# OPA4377.net
KiCad netlist of a schematic drawn in Altium Designer
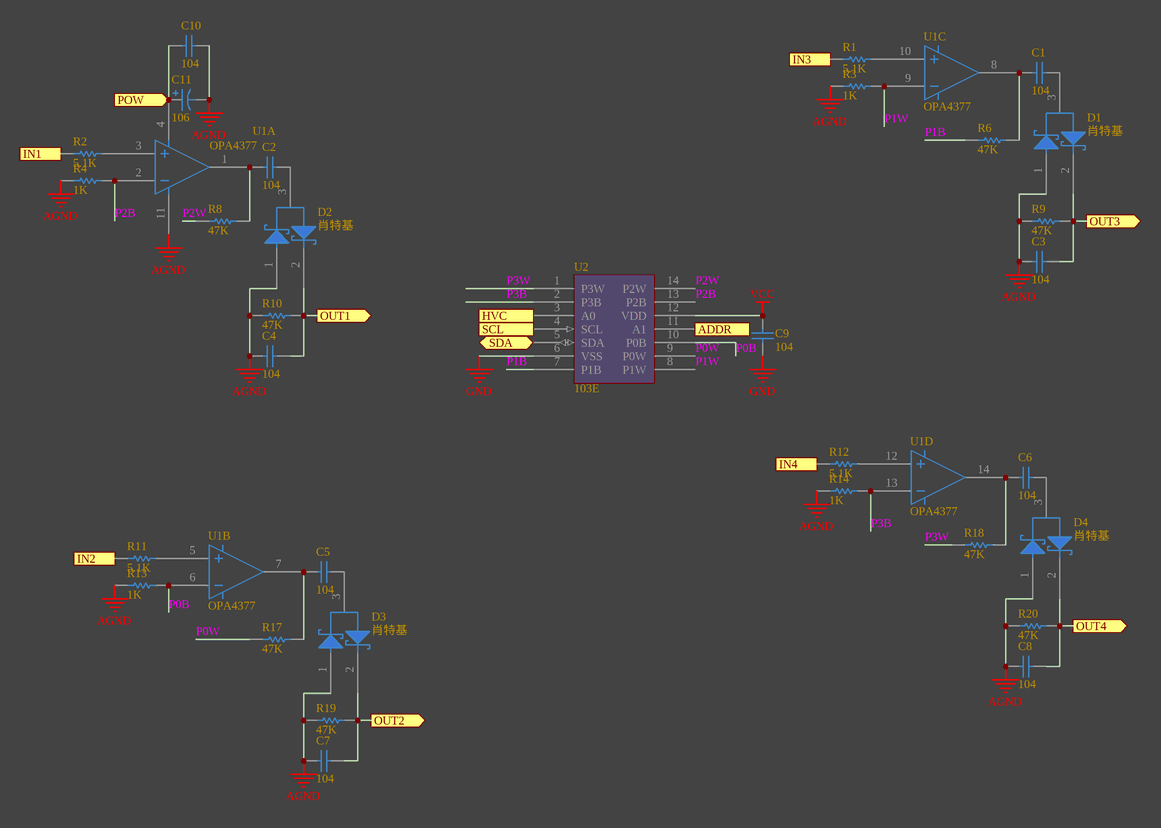
[diagram p0: OPA4377.SchDoc]

(export (version "E")
  (design (tool "Eeschema 10.0.6"))
  (components
    (comp (ref "C1")
      (value "104")
      (footprint "C0402")
      (description "Capacitor")
      (fields (field (name "PUBLISHER") "Altium Limited"))
      (libsource (lib "iMag") (part "电容"))
    )
    (comp (ref "C2")
      (value "104")
      (footprint "C0402")
      (description "Capacitor")
      (fields (field (name "PUBLISHER") "Altium Limited"))
      (libsource (lib "iMag") (part "电容"))
    )
    (comp (ref "C3")
      (value "104")
      (footprint "C0402")
      (description "Capacitor")
      (fields (field (name "PUBLISHER") "Altium Limited"))
      (libsource (lib "iMag") (part "电容"))
    )
    (comp (ref "C4")
      (value "104")
      (footprint "C0402")
      (description "Capacitor")
      (fields (field (name "PUBLISHER") "Altium Limited"))
      (libsource (lib "iMag") (part "电容"))
    )
    (comp (ref "C5")
      (value "104")
      (footprint "C0402")
      (description "Capacitor")
      (fields (field (name "PUBLISHER") "Altium Limited"))
      (libsource (lib "iMag") (part "电容"))
    )
    (comp (ref "C6")
      (value "104")
      (footprint "C0402")
      (description "Capacitor")
      (fields (field (name "PUBLISHER") "Altium Limited"))
      (libsource (lib "iMag") (part "电容"))
    )
    (comp (ref "C7")
      (value "104")
      (footprint "C0402")
      (description "Capacitor")
      (fields (field (name "PUBLISHER") "Altium Limited"))
      (libsource (lib "iMag") (part "电容"))
    )
    (comp (ref "C8")
      (value "104")
      (footprint "C0402")
      (description "Capacitor")
      (fields (field (name "PUBLISHER") "Altium Limited"))
      (libsource (lib "iMag") (part "电容"))
    )
    (comp (ref "C9")
      (value "104")
      (footprint "C0402")
      (description "Capacitor")
      (fields (field (name "PUBLISHER") "Altium Limited"))
      (libsource (lib "iMag") (part "电容"))
    )
    (comp (ref "C10")
      (value "104")
      (footprint "C0402")
      (description "Capacitor")
      (fields (field (name "PUBLISHER") "Altium Limited"))
      (libsource (lib "iMag") (part "电容"))
    )
    (comp (ref "C11")
      (value "106")
      (footprint "3216-ce")
      (description "Polarized Capacitor (Axial)")
      (fields (field (name "PUBLISHER") "Altium Limited"))
      (libsource (lib "iMag") (part "电解电容"))
    )
    (comp (ref "D1") (value "肖特基") (footprint "SOT-23") (libsource (lib "iMag") (part "BAT54S")))
    (comp (ref "D2") (value "肖特基") (footprint "SOT-23") (libsource (lib "iMag") (part "BAT54S")))
    (comp (ref "D3") (value "肖特基") (footprint "SOT-23") (libsource (lib "iMag") (part "BAT54S")))
    (comp (ref "D4") (value "肖特基") (footprint "SOT-23") (libsource (lib "iMag") (part "BAT54S")))
    (comp (ref "R1")
      (value "5.1K")
      (footprint "R0402")
      (description "Resistor")
      (fields (field (name "PUBLISHER") "Altium Limited"))
      (libsource (lib "iMag") (part "电阻"))
    )
    (comp (ref "R2")
      (value "5.1K")
      (footprint "R0402")
      (description "Resistor")
      (fields (field (name "PUBLISHER") "Altium Limited"))
      (libsource (lib "iMag") (part "电阻"))
    )
    (comp (ref "R3")
      (value "1K")
      (footprint "R0402")
      (description "Resistor")
      (fields (field (name "PUBLISHER") "Altium Limited"))
      (libsource (lib "iMag") (part "电阻"))
    )
    (comp (ref "R4")
      (value "1K")
      (footprint "R0402")
      (description "Resistor")
      (fields (field (name "PUBLISHER") "Altium Limited"))
      (libsource (lib "iMag") (part "电阻"))
    )
    (comp (ref "R6")
      (value "47K")
      (footprint "R0402")
      (description "Resistor")
      (fields (field (name "PUBLISHER") "Altium Limited"))
      (libsource (lib "iMag") (part "电阻"))
    )
    (comp (ref "R8")
      (value "47K")
      (footprint "R0402")
      (description "Resistor")
      (fields (field (name "PUBLISHER") "Altium Limited"))
      (libsource (lib "iMag") (part "电阻"))
    )
    (comp (ref "R9")
      (value "47K")
      (footprint "R0402")
      (description "Resistor")
      (fields (field (name "PUBLISHER") "Altium Limited"))
      (libsource (lib "iMag") (part "电阻"))
    )
    (comp (ref "R10")
      (value "47K")
      (footprint "R0402")
      (description "Resistor")
      (fields (field (name "PUBLISHER") "Altium Limited"))
      (libsource (lib "iMag") (part "电阻"))
    )
    (comp (ref "R11")
      (value "5.1K")
      (footprint "R0402")
      (description "Resistor")
      (fields (field (name "PUBLISHER") "Altium Limited"))
      (libsource (lib "iMag") (part "电阻"))
    )
    (comp (ref "R12")
      (value "5.1K")
      (footprint "R0402")
      (description "Resistor")
      (fields (field (name "PUBLISHER") "Altium Limited"))
      (libsource (lib "iMag") (part "电阻"))
    )
    (comp (ref "R13")
      (value "1K")
      (footprint "R0402")
      (description "Resistor")
      (fields (field (name "PUBLISHER") "Altium Limited"))
      (libsource (lib "iMag") (part "电阻"))
    )
    (comp (ref "R14")
      (value "1K")
      (footprint "R0402")
      (description "Resistor")
      (fields (field (name "PUBLISHER") "Altium Limited"))
      (libsource (lib "iMag") (part "电阻"))
    )
    (comp (ref "R17")
      (value "47K")
      (footprint "R0402")
      (description "Resistor")
      (fields (field (name "PUBLISHER") "Altium Limited"))
      (libsource (lib "iMag") (part "电阻"))
    )
    (comp (ref "R18")
      (value "47K")
      (footprint "R0402")
      (description "Resistor")
      (fields (field (name "PUBLISHER") "Altium Limited"))
      (libsource (lib "iMag") (part "电阻"))
    )
    (comp (ref "R19")
      (value "47K")
      (footprint "R0402")
      (description "Resistor")
      (fields (field (name "PUBLISHER") "Altium Limited"))
      (libsource (lib "iMag") (part "电阻"))
    )
    (comp (ref "R20")
      (value "47K")
      (footprint "R0402")
      (description "Resistor")
      (fields (field (name "PUBLISHER") "Altium Limited"))
      (libsource (lib "iMag") (part "电阻"))
    )
    (comp (ref "U1") (value "OPA4377") (footprint "TSSOP-14") (libsource (lib "iMag") (part "4运放")))
    (comp (ref "U2") (value "103E") (footprint "TSSOP-14") (libsource (lib "iMag") (part "MCP4452")))
  )
  (nets
    (net (code "1") (name "/ADDR") (class "Default")
      (node (ref "U2") (pin "11") (pinfunction "A1_11") (pintype "passive"))
    )
    (net (code "2") (name "/HVC") (class "Default")
      (node (ref "U2") (pin "3") (pinfunction "A0_3") (pintype "passive"))
    )
    (net (code "3") (name "/IN1") (class "Default")
      (node (ref "R2") (pin "2") (pinfunction "2_2") (pintype "passive"))
    )
    (net (code "4") (name "/IN2") (class "Default")
      (node (ref "R11") (pin "2") (pinfunction "2_2") (pintype "passive"))
    )
    (net (code "5") (name "/IN3") (class "Default")
      (node (ref "R1") (pin "2") (pinfunction "2_2") (pintype "passive"))
    )
    (net (code "6") (name "/IN4") (class "Default")
      (node (ref "R12") (pin "2") (pinfunction "2_2") (pintype "passive"))
    )
    (net (code "7") (name "/OUT1") (class "Default")
      (node (ref "C4") (pin "2") (pinfunction "2_2") (pintype "passive"))
      (node (ref "D2") (pin "2") (pinfunction "2_2") (pintype "passive"))
      (node (ref "R10") (pin "1") (pinfunction "1_1") (pintype "passive"))
    )
    (net (code "8") (name "/OUT2") (class "Default")
      (node (ref "C7") (pin "2") (pinfunction "2_2") (pintype "passive"))
      (node (ref "D3") (pin "2") (pinfunction "2_2") (pintype "passive"))
      (node (ref "R19") (pin "1") (pinfunction "1_1") (pintype "passive"))
    )
    (net (code "9") (name "/OUT3") (class "Default")
      (node (ref "C3") (pin "2") (pinfunction "2_2") (pintype "passive"))
      (node (ref "D1") (pin "2") (pinfunction "2_2") (pintype "passive"))
      (node (ref "R9") (pin "1") (pinfunction "1_1") (pintype "passive"))
    )
    (net (code "10") (name "/OUT4") (class "Default")
      (node (ref "C8") (pin "2") (pinfunction "2_2") (pintype "passive"))
      (node (ref "D4") (pin "2") (pinfunction "2_2") (pintype "passive"))
      (node (ref "R20") (pin "1") (pinfunction "1_1") (pintype "passive"))
    )
    (net (code "11") (name "/P0B") (class "Default")
      (node (ref "R13") (pin "1") (pinfunction "1_1") (pintype "passive"))
      (node (ref "U1") (pin "6") (pintype "passive"))
      (node (ref "U2") (pin "10") (pinfunction "P0B_10") (pintype "passive"))
    )
    (net (code "12") (name "/P0W") (class "Default")
      (node (ref "R17") (pin "2") (pinfunction "2_2") (pintype "passive"))
      (node (ref "U2") (pin "9") (pinfunction "P0W_9") (pintype "passive"))
    )
    (net (code "13") (name "/P1B") (class "Default")
      (node (ref "R6") (pin "2") (pinfunction "2_2") (pintype "passive"))
      (node (ref "U2") (pin "7") (pinfunction "P1B_7") (pintype "passive"))
    )
    (net (code "14") (name "/P1W") (class "Default")
      (node (ref "R3") (pin "1") (pinfunction "1_1") (pintype "passive"))
      (node (ref "U1") (pin "9") (pintype "passive"))
      (node (ref "U2") (pin "8") (pinfunction "P1W_8") (pintype "passive"))
    )
    (net (code "15") (name "/P2B") (class "Default")
      (node (ref "R4") (pin "1") (pinfunction "1_1") (pintype "passive"))
      (node (ref "U1") (pin "2") (pintype "passive"))
      (node (ref "U2") (pin "13") (pinfunction "P2B_13") (pintype "passive"))
    )
    (net (code "16") (name "/P2W") (class "Default")
      (node (ref "R8") (pin "2") (pinfunction "2_2") (pintype "passive"))
      (node (ref "U2") (pin "14") (pinfunction "P2W_14") (pintype "passive"))
    )
    (net (code "17") (name "/P3B") (class "Default")
      (node (ref "R14") (pin "1") (pinfunction "1_1") (pintype "passive"))
      (node (ref "U1") (pin "13") (pintype "passive"))
      (node (ref "U2") (pin "2") (pinfunction "P3B_2") (pintype "passive"))
    )
    (net (code "18") (name "/P3W") (class "Default")
      (node (ref "R18") (pin "2") (pinfunction "2_2") (pintype "passive"))
      (node (ref "U2") (pin "1") (pinfunction "P3W_1") (pintype "passive"))
    )
    (net (code "19") (name "/POW") (class "Default")
      (node (ref "C10") (pin "1") (pinfunction "1_1") (pintype "passive"))
      (node (ref "C11") (pin "1") (pinfunction "1_1") (pintype "passive"))
      (node (ref "U1") (pin "4") (pintype "passive"))
    )
    (net (code "20") (name "/SCL") (class "Default")
      (node (ref "U2") (pin "4") (pinfunction "SCL_4") (pintype "input"))
    )
    (net (code "21") (name "/SDA") (class "Default")
      (node (ref "U2") (pin "5") (pinfunction "SDA_5") (pintype "bidirectional"))
    )
    (net (code "22") (name "AGND") (class "Default")
      (node (ref "C10") (pin "2") (pinfunction "2_2") (pintype "passive"))
      (node (ref "C11") (pin "2") (pinfunction "2_2") (pintype "passive"))
      (node (ref "C3") (pin "1") (pinfunction "1_1") (pintype "passive"))
      (node (ref "C4") (pin "1") (pinfunction "1_1") (pintype "passive"))
      (node (ref "C7") (pin "1") (pinfunction "1_1") (pintype "passive"))
      (node (ref "C8") (pin "1") (pinfunction "1_1") (pintype "passive"))
      (node (ref "D1") (pin "1") (pinfunction "1_1") (pintype "passive"))
      (node (ref "D2") (pin "1") (pinfunction "1_1") (pintype "passive"))
      (node (ref "D3") (pin "1") (pinfunction "1_1") (pintype "passive"))
      (node (ref "D4") (pin "1") (pinfunction "1_1") (pintype "passive"))
      (node (ref "R10") (pin "2") (pinfunction "2_2") (pintype "passive"))
      (node (ref "R13") (pin "2") (pinfunction "2_2") (pintype "passive"))
      (node (ref "R14") (pin "2") (pinfunction "2_2") (pintype "passive"))
      (node (ref "R19") (pin "2") (pinfunction "2_2") (pintype "passive"))
      (node (ref "R20") (pin "2") (pinfunction "2_2") (pintype "passive"))
      (node (ref "R3") (pin "2") (pinfunction "2_2") (pintype "passive"))
      (node (ref "R4") (pin "2") (pinfunction "2_2") (pintype "passive"))
      (node (ref "R9") (pin "2") (pinfunction "2_2") (pintype "passive"))
      (node (ref "U1") (pin "11") (pintype "passive"))
    )
    (net (code "23") (name "GND") (class "Default")
      (node (ref "C9") (pin "1") (pinfunction "1_1") (pintype "passive"))
      (node (ref "U2") (pin "6") (pinfunction "VSS_6") (pintype "passive"))
    )
    (net (code "24") (name "Net-(C1-Pad1)") (class "Default")
      (node (ref "C1") (pin "1") (pinfunction "1_1") (pintype "passive"))
      (node (ref "R6") (pin "1") (pinfunction "1_1") (pintype "passive"))
      (node (ref "U1") (pin "8") (pintype "passive"))
    )
    (net (code "25") (name "Net-(C1-Pad2)") (class "Default")
      (node (ref "C1") (pin "2") (pinfunction "2_2") (pintype "passive"))
      (node (ref "D1") (pin "3") (pinfunction "3_3") (pintype "passive"))
    )
    (net (code "26") (name "Net-(C2-Pad1)") (class "Default")
      (node (ref "C2") (pin "1") (pinfunction "1_1") (pintype "passive"))
      (node (ref "R8") (pin "1") (pinfunction "1_1") (pintype "passive"))
      (node (ref "U1") (pin "1") (pintype "passive"))
    )
    (net (code "27") (name "Net-(C2-Pad2)") (class "Default")
      (node (ref "C2") (pin "2") (pinfunction "2_2") (pintype "passive"))
      (node (ref "D2") (pin "3") (pinfunction "3_3") (pintype "passive"))
    )
    (net (code "28") (name "Net-(C5-Pad1)") (class "Default")
      (node (ref "C5") (pin "1") (pinfunction "1_1") (pintype "passive"))
      (node (ref "R17") (pin "1") (pinfunction "1_1") (pintype "passive"))
      (node (ref "U1") (pin "7") (pintype "passive"))
    )
    (net (code "29") (name "Net-(C5-Pad2)") (class "Default")
      (node (ref "C5") (pin "2") (pinfunction "2_2") (pintype "passive"))
      (node (ref "D3") (pin "3") (pinfunction "3_3") (pintype "passive"))
    )
    (net (code "30") (name "Net-(C6-Pad1)") (class "Default")
      (node (ref "C6") (pin "1") (pinfunction "1_1") (pintype "passive"))
      (node (ref "R18") (pin "1") (pinfunction "1_1") (pintype "passive"))
      (node (ref "U1") (pin "14") (pintype "passive"))
    )
    (net (code "31") (name "Net-(C6-Pad2)") (class "Default")
      (node (ref "C6") (pin "2") (pinfunction "2_2") (pintype "passive"))
      (node (ref "D4") (pin "3") (pinfunction "3_3") (pintype "passive"))
    )
    (net (code "32") (name "Net-(R1-Pad1)") (class "Default")
      (node (ref "R1") (pin "1") (pinfunction "1_1") (pintype "passive"))
      (node (ref "U1") (pin "10") (pintype "passive"))
    )
    (net (code "33") (name "Net-(R2-Pad1)") (class "Default")
      (node (ref "R2") (pin "1") (pinfunction "1_1") (pintype "passive"))
      (node (ref "U1") (pin "3") (pintype "passive"))
    )
    (net (code "34") (name "Net-(R11-Pad1)") (class "Default")
      (node (ref "R11") (pin "1") (pinfunction "1_1") (pintype "passive"))
      (node (ref "U1") (pin "5") (pintype "passive"))
    )
    (net (code "35") (name "Net-(R12-Pad1)") (class "Default")
      (node (ref "R12") (pin "1") (pinfunction "1_1") (pintype "passive"))
      (node (ref "U1") (pin "12") (pintype "passive"))
    )
    (net (code "36") (name "VCC") (class "Default")
      (node (ref "C9") (pin "2") (pinfunction "2_2") (pintype "passive"))
      (node (ref "U2") (pin "12") (pinfunction "VDD_12") (pintype "passive"))
    )
  )
)
